# Interfaces.net
KiCad netlist of a schematic drawn in Altium Designer
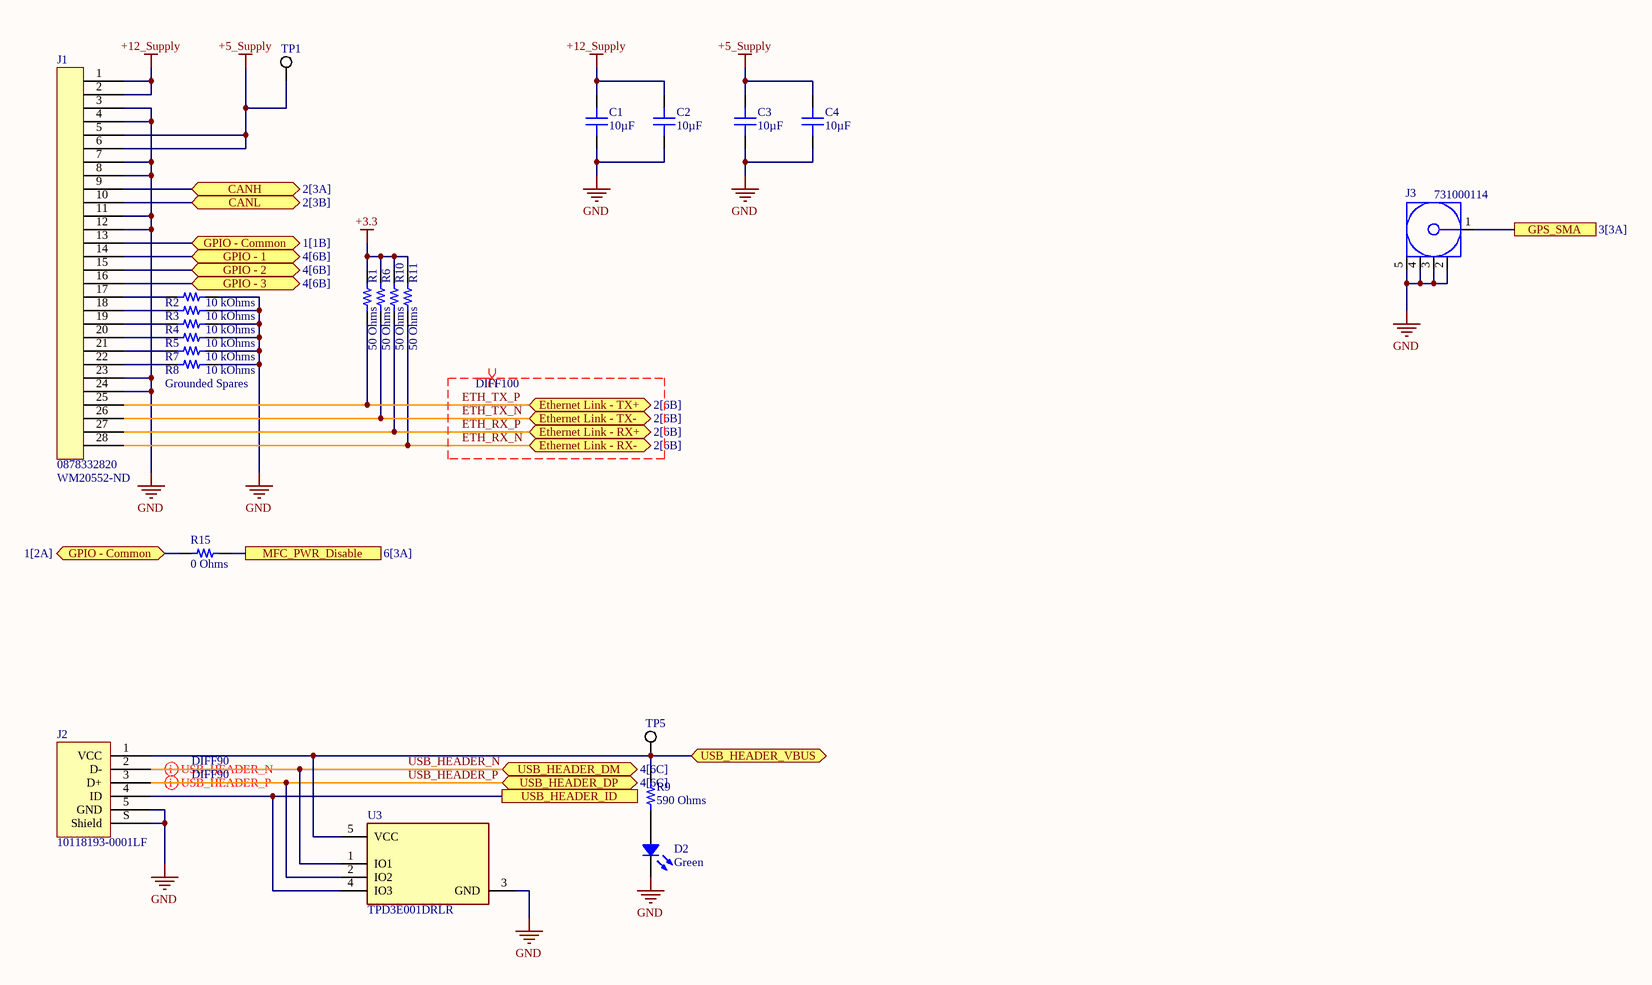
[diagram p0: Interfaces.SchDoc]

(export (version "E")
  (design (tool "Eeschema 10.0.6"))
  (components
    (comp (ref "C1")
      (value "10µF")
      (footprint "CAP 0805_2012")
      (description "CAP CER 10UF 16V X5R 0805")
      (fields (field (name "PART NUMBER") "CC0805KKX5R7BB106") (field (name "MANUFACTURER") "Yageo"))
      (libsource (lib "Celestial Altium Library - altium_library") (part "Capacitor"))
    )
    (comp (ref "C2")
      (value "10µF")
      (footprint "CAP 0805_2012")
      (description "CAP CER 10UF 16V X5R 0805")
      (fields (field (name "PART NUMBER") "CC0805KKX5R7BB106") (field (name "MANUFACTURER") "Yageo"))
      (libsource (lib "Celestial Altium Library - altium_library") (part "Capacitor"))
    )
    (comp (ref "C3")
      (value "10µF")
      (footprint "CAP 0805_2012")
      (description "CAP CER 10UF 16V X5R 0805")
      (fields (field (name "PART NUMBER") "CC0805KKX5R7BB106") (field (name "MANUFACTURER") "Yageo"))
      (libsource (lib "Celestial Altium Library - altium_library") (part "Capacitor"))
    )
    (comp (ref "C4")
      (value "10µF")
      (footprint "CAP 0805_2012")
      (description "CAP CER 10UF 16V X5R 0805")
      (fields (field (name "PART NUMBER") "CC0805KKX5R7BB106") (field (name "MANUFACTURER") "Yageo"))
      (libsource (lib "Celestial Altium Library - altium_library") (part "Capacitor"))
    )
    (comp (ref "D2")
      (value "Green")
      (footprint "LED 0603_1608 GREEN")
      (description "LED GREEN CLEAR CHIP SMD")
      (fields (field (name "PART NUMBER") "LTST-C193KGKT-5A") (field (name "MANUFACTURER") "Lite-On Inc."))
      (libsource (lib "Celestial Altium Library - altium_library") (part "LED"))
    )
    (comp (ref "J1")
      (value "0878332820")
      (footprint "0878332820")
      (fields (field (name "SUPPLIER PART NUMBER 1") "WM20552-ND"))
      (libsource (lib "HAB_Connectors") (part "0878332820"))
    )
    (comp (ref "J2")
      (value "10118193-0001LF")
      (footprint "FCI USB 10118193-0001LF")
      (description "CONN RCPT USB2.0 MICRO B SMD R/A")
      (fields (field (name "MANUFACTURER") "Amphenol ICC (FCI)"))
      (libsource (lib "Celestial Altium Library - altium_library") (part "USB 2.0 Type B Micro"))
    )
    (comp (ref "J3")
      (value "731000114")
      (footprint "MOLX-731000114_V")
      (description "SMA Right-Angle PCB Jack Receptacle, Brass Body, Gold Plated, 50 Ohm, 5-Pin THD, RoHS, Tray")
      (fields (field (name "MANUFACTURER") "Molex"))
      (libsource (lib "Altium Content Vault") (part "CN-S-4F-RF5"))
    )
    (comp (ref "R1")
      (value "50 Ohms")
      (footprint "RES 0603_1608")
      (description "RES SMD 50 OHM 1% 1/10W 0603")
      (fields (field (name "PART NUMBER") "CRCW060350R0FKEA") (field (name "MANUFACTURER") "Vishay Dale"))
      (libsource (lib "Celestial Altium Library - altium_library") (part "Resistor"))
    )
    (comp (ref "R2")
      (value "10 kOhms")
      (footprint "RES 0603_1608")
      (description "RES 10K OHM 5% 1/10W 0603")
      (fields
        (field (name "PART NUMBER") "RMCF0603JT10K0")
        (field (name "MANUFACTURER") "Stackpole Electronics Inc")
      )
      (libsource (lib "Celestial Altium Library - altium_library") (part "Resistor"))
    )
    (comp (ref "R3")
      (value "10 kOhms")
      (footprint "RES 0603_1608")
      (description "RES 10K OHM 5% 1/10W 0603")
      (fields
        (field (name "PART NUMBER") "RMCF0603JT10K0")
        (field (name "MANUFACTURER") "Stackpole Electronics Inc")
      )
      (libsource (lib "Celestial Altium Library - altium_library") (part "Resistor"))
    )
    (comp (ref "R4")
      (value "10 kOhms")
      (footprint "RES 0603_1608")
      (description "RES 10K OHM 5% 1/10W 0603")
      (fields
        (field (name "PART NUMBER") "RMCF0603JT10K0")
        (field (name "MANUFACTURER") "Stackpole Electronics Inc")
      )
      (libsource (lib "Celestial Altium Library - altium_library") (part "Resistor"))
    )
    (comp (ref "R5")
      (value "10 kOhms")
      (footprint "RES 0603_1608")
      (description "RES 10K OHM 5% 1/10W 0603")
      (fields
        (field (name "PART NUMBER") "RMCF0603JT10K0")
        (field (name "MANUFACTURER") "Stackpole Electronics Inc")
      )
      (libsource (lib "Celestial Altium Library - altium_library") (part "Resistor"))
    )
    (comp (ref "R6")
      (value "50 Ohms")
      (footprint "RES 0603_1608")
      (description "RES SMD 50 OHM 1% 1/10W 0603")
      (fields (field (name "PART NUMBER") "CRCW060350R0FKEA") (field (name "MANUFACTURER") "Vishay Dale"))
      (libsource (lib "Celestial Altium Library - altium_library") (part "Resistor"))
    )
    (comp (ref "R7")
      (value "10 kOhms")
      (footprint "RES 0603_1608")
      (description "RES 10K OHM 5% 1/10W 0603")
      (fields
        (field (name "PART NUMBER") "RMCF0603JT10K0")
        (field (name "MANUFACTURER") "Stackpole Electronics Inc")
      )
      (libsource (lib "Celestial Altium Library - altium_library") (part "Resistor"))
    )
    (comp (ref "R8")
      (value "10 kOhms")
      (footprint "RES 0603_1608")
      (description "RES 10K OHM 5% 1/10W 0603")
      (fields
        (field (name "PART NUMBER") "RMCF0603JT10K0")
        (field (name "MANUFACTURER") "Stackpole Electronics Inc")
      )
      (libsource (lib "Celestial Altium Library - altium_library") (part "Resistor"))
    )
    (comp (ref "R9")
      (value "590 Ohms")
      (footprint "RES 0603_1608")
      (description "RES 590 OHM 1% 1/10W 0603")
      (fields
        (field (name "PART NUMBER") "RMCF0603FT590R")
        (field (name "MANUFACTURER") "Stackpole Electronics Inc")
      )
      (libsource (lib "Celestial Altium Library - altium_library") (part "Resistor"))
    )
    (comp (ref "R10")
      (value "50 Ohms")
      (footprint "RES 0603_1608")
      (description "RES SMD 50 OHM 1% 1/10W 0603")
      (fields (field (name "PART NUMBER") "CRCW060350R0FKEA") (field (name "MANUFACTURER") "Vishay Dale"))
      (libsource (lib "Celestial Altium Library - altium_library") (part "Resistor"))
    )
    (comp (ref "R11")
      (value "50 Ohms")
      (footprint "RES 0603_1608")
      (description "RES SMD 50 OHM 1% 1/10W 0603")
      (fields (field (name "PART NUMBER") "CRCW060350R0FKEA") (field (name "MANUFACTURER") "Vishay Dale"))
      (libsource (lib "Celestial Altium Library - altium_library") (part "Resistor"))
    )
    (comp (ref "R15")
      (value "0 Ohms")
      (footprint "RES 0603_1608")
      (description "RES 0 OHM JUMPER 1/10W 0603")
      (fields
        (field (name "PART NUMBER") "RMCF0603ZT0R00")
        (field (name "MANUFACTURER") "Stackpole Electronics Inc")
      )
      (libsource (lib "Celestial Altium Library - altium_library") (part "Resistor"))
    )
    (comp (ref "TP1")
      (value "5019")
      (footprint "KSTN-5019_V")
      (description "Test Point, 1 Position SMD, RoHS, Tape and Reel")
      (libsource (lib "Altium Content Vault") (part "TESTPOINT_WHITE"))
    )
    (comp (ref "TP5")
      (value "5019")
      (footprint "KSTN-5019_V")
      (description "Test Point, 1 Position SMD, RoHS, Tape and Reel")
      (libsource (lib "Altium Content Vault") (part "TESTPOINT_WHITE"))
    )
    (comp (ref "U3")
      (value "TPD3E001DRLR")
      (footprint "FP-DRL0005A-MFG")
      (description "TVS DIODE 5.5V SOT5")
      (libsource (lib "Altium Content Vault") (part "867ba43d99b3a33c275ad84274a843c"))
    )
  )
  (nets
    (net (code "1") (name "+3.3") (class "Default")
      (node (ref "R1") (pin "2") (pinfunction "2_2") (pintype "passive"))
      (node (ref "R10") (pin "2") (pinfunction "2_2") (pintype "passive"))
      (node (ref "R11") (pin "2") (pinfunction "2_2") (pintype "passive"))
      (node (ref "R6") (pin "2") (pinfunction "2_2") (pintype "passive"))
    )
    (net (code "2") (name "+5_Supply") (class "Default")
      (node (ref "C3") (pin "2") (pinfunction "2_2") (pintype "passive"))
      (node (ref "C4") (pin "2") (pinfunction "2_2") (pintype "passive"))
      (node (ref "J1") (pin "5") (pintype "passive"))
      (node (ref "J1") (pin "6") (pintype "passive"))
      (node (ref "TP1") (pin "1") (pinfunction "1_1") (pintype "passive"))
    )
    (net (code "3") (name "+12_Supply") (class "Default")
      (node (ref "C1") (pin "2") (pinfunction "2_2") (pintype "passive"))
      (node (ref "C2") (pin "2") (pinfunction "2_2") (pintype "passive"))
      (node (ref "J1") (pin "1") (pintype "passive"))
      (node (ref "J1") (pin "2") (pintype "passive"))
    )
    (net (code "4") (name "/CANH") (class "Default") (node (ref "J1") (pin "9") (pintype "passive")))
    (net (code "5") (name "/CANL") (class "Default") (node (ref "J1") (pin "10") (pintype "passive")))
    (net (code "6") (name "/ETH_RX_N") (class "Default")
      (node (ref "J1") (pin "28") (pintype "passive"))
      (node (ref "R11") (pin "1") (pinfunction "1_1") (pintype "passive"))
    )
    (net (code "7") (name "/ETH_RX_P") (class "Default")
      (node (ref "J1") (pin "27") (pintype "passive"))
      (node (ref "R10") (pin "1") (pinfunction "1_1") (pintype "passive"))
    )
    (net (code "8") (name "/ETH_TX_N") (class "Default")
      (node (ref "J1") (pin "26") (pintype "passive"))
      (node (ref "R6") (pin "1") (pinfunction "1_1") (pintype "passive"))
    )
    (net (code "9") (name "/ETH_TX_P") (class "Default")
      (node (ref "J1") (pin "25") (pintype "passive"))
      (node (ref "R1") (pin "1") (pinfunction "1_1") (pintype "passive"))
    )
    (net (code "10") (name "/GPIO - 1") (class "Default") (node (ref "J1") (pin "14") (pintype "passive")))
    (net (code "11") (name "/GPIO - 2") (class "Default") (node (ref "J1") (pin "15") (pintype "passive")))
    (net (code "12") (name "/GPIO - 3") (class "Default") (node (ref "J1") (pin "16") (pintype "passive")))
    (net (code "13") (name "/GPIO - Common") (class "Default")
      (node (ref "J1") (pin "13") (pintype "passive"))
      (node (ref "R15") (pin "1") (pinfunction "1_1") (pintype "passive"))
    )
    (net (code "14") (name "/GPS_SMA") (class "Default")
      (node (ref "J3") (pin "1") (pinfunction "1_1") (pintype "passive"))
    )
    (net (code "15") (name "/MFC_PWR_Disable") (class "Default")
      (node (ref "R15") (pin "2") (pinfunction "2_2") (pintype "passive"))
    )
    (net (code "16") (name "/USB_HEADER_ID") (class "Default")
      (node (ref "J2") (pin "4") (pinfunction "ID_4") (pintype "passive"))
      (node (ref "U3") (pin "4") (pinfunction "IO3_4") (pintype "passive"))
    )
    (net (code "17") (name "/USB_HEADER_N") (class "Default")
      (node (ref "J2") (pin "2") (pinfunction "D-_2") (pintype "passive"))
      (node (ref "U3") (pin "1") (pinfunction "IO1_1") (pintype "passive"))
    )
    (net (code "18") (name "/USB_HEADER_P") (class "Default")
      (node (ref "J2") (pin "3") (pinfunction "D+_3") (pintype "passive"))
      (node (ref "U3") (pin "2") (pinfunction "IO2_2") (pintype "passive"))
    )
    (net (code "19") (name "/USB_HEADER_VBUS") (class "Default")
      (node (ref "J2") (pin "1") (pinfunction "VCC_1") (pintype "passive"))
      (node (ref "R9") (pin "2") (pinfunction "2_2") (pintype "passive"))
      (node (ref "TP5") (pin "1") (pinfunction "1_1") (pintype "passive"))
      (node (ref "U3") (pin "5") (pinfunction "VCC_5") (pintype "power_in"))
    )
    (net (code "20") (name "GND") (class "Default")
      (node (ref "C1") (pin "1") (pinfunction "1_1") (pintype "passive"))
      (node (ref "C2") (pin "1") (pinfunction "1_1") (pintype "passive"))
      (node (ref "C3") (pin "1") (pinfunction "1_1") (pintype "passive"))
      (node (ref "C4") (pin "1") (pinfunction "1_1") (pintype "passive"))
      (node (ref "D2") (pin "2") (pinfunction "2_2") (pintype "passive"))
      (node (ref "J1") (pin "11") (pintype "passive"))
      (node (ref "J1") (pin "12") (pintype "passive"))
      (node (ref "J1") (pin "23") (pintype "passive"))
      (node (ref "J1") (pin "24") (pintype "passive"))
      (node (ref "J1") (pin "3") (pintype "passive"))
      (node (ref "J1") (pin "4") (pintype "passive"))
      (node (ref "J1") (pin "7") (pintype "passive"))
      (node (ref "J1") (pin "8") (pintype "passive"))
      (node (ref "J2") (pin "5") (pinfunction "GND_5") (pintype "passive"))
      (node (ref "J2") (pin "S") (pinfunction "Shield_S") (pintype "passive"))
      (node (ref "J3") (pin "2") (pinfunction "2_2") (pintype "passive"))
      (node (ref "J3") (pin "3") (pinfunction "3_3") (pintype "passive"))
      (node (ref "J3") (pin "4") (pinfunction "4_4") (pintype "passive"))
      (node (ref "J3") (pin "5") (pinfunction "5_5") (pintype "passive"))
      (node (ref "R2") (pin "2") (pinfunction "2_2") (pintype "passive"))
      (node (ref "R3") (pin "2") (pinfunction "2_2") (pintype "passive"))
      (node (ref "R4") (pin "2") (pinfunction "2_2") (pintype "passive"))
      (node (ref "R5") (pin "2") (pinfunction "2_2") (pintype "passive"))
      (node (ref "R7") (pin "2") (pinfunction "2_2") (pintype "passive"))
      (node (ref "R8") (pin "2") (pinfunction "2_2") (pintype "passive"))
      (node (ref "U3") (pin "3") (pinfunction "GND_3") (pintype "power_in"))
    )
    (net (code "21") (name "Net-(D2-Pad1)") (class "Default")
      (node (ref "D2") (pin "1") (pinfunction "1_1") (pintype "passive"))
      (node (ref "R9") (pin "1") (pinfunction "1_1") (pintype "passive"))
    )
    (net (code "22") (name "Net-(J1-Pad17)") (class "Default")
      (node (ref "J1") (pin "17") (pintype "passive"))
      (node (ref "R2") (pin "1") (pinfunction "1_1") (pintype "passive"))
    )
    (net (code "23") (name "Net-(J1-Pad18)") (class "Default")
      (node (ref "J1") (pin "18") (pintype "passive"))
      (node (ref "R3") (pin "1") (pinfunction "1_1") (pintype "passive"))
    )
    (net (code "24") (name "Net-(J1-Pad19)") (class "Default")
      (node (ref "J1") (pin "19") (pintype "passive"))
      (node (ref "R4") (pin "1") (pinfunction "1_1") (pintype "passive"))
    )
    (net (code "25") (name "Net-(J1-Pad20)") (class "Default")
      (node (ref "J1") (pin "20") (pintype "passive"))
      (node (ref "R5") (pin "1") (pinfunction "1_1") (pintype "passive"))
    )
    (net (code "26") (name "Net-(J1-Pad21)") (class "Default")
      (node (ref "J1") (pin "21") (pintype "passive"))
      (node (ref "R7") (pin "1") (pinfunction "1_1") (pintype "passive"))
    )
    (net (code "27") (name "Net-(J1-Pad22)") (class "Default")
      (node (ref "J1") (pin "22") (pintype "passive"))
      (node (ref "R8") (pin "1") (pinfunction "1_1") (pintype "passive"))
    )
  )
)
